# template.net
KiCad netlist of a schematic drawn in EAGLE
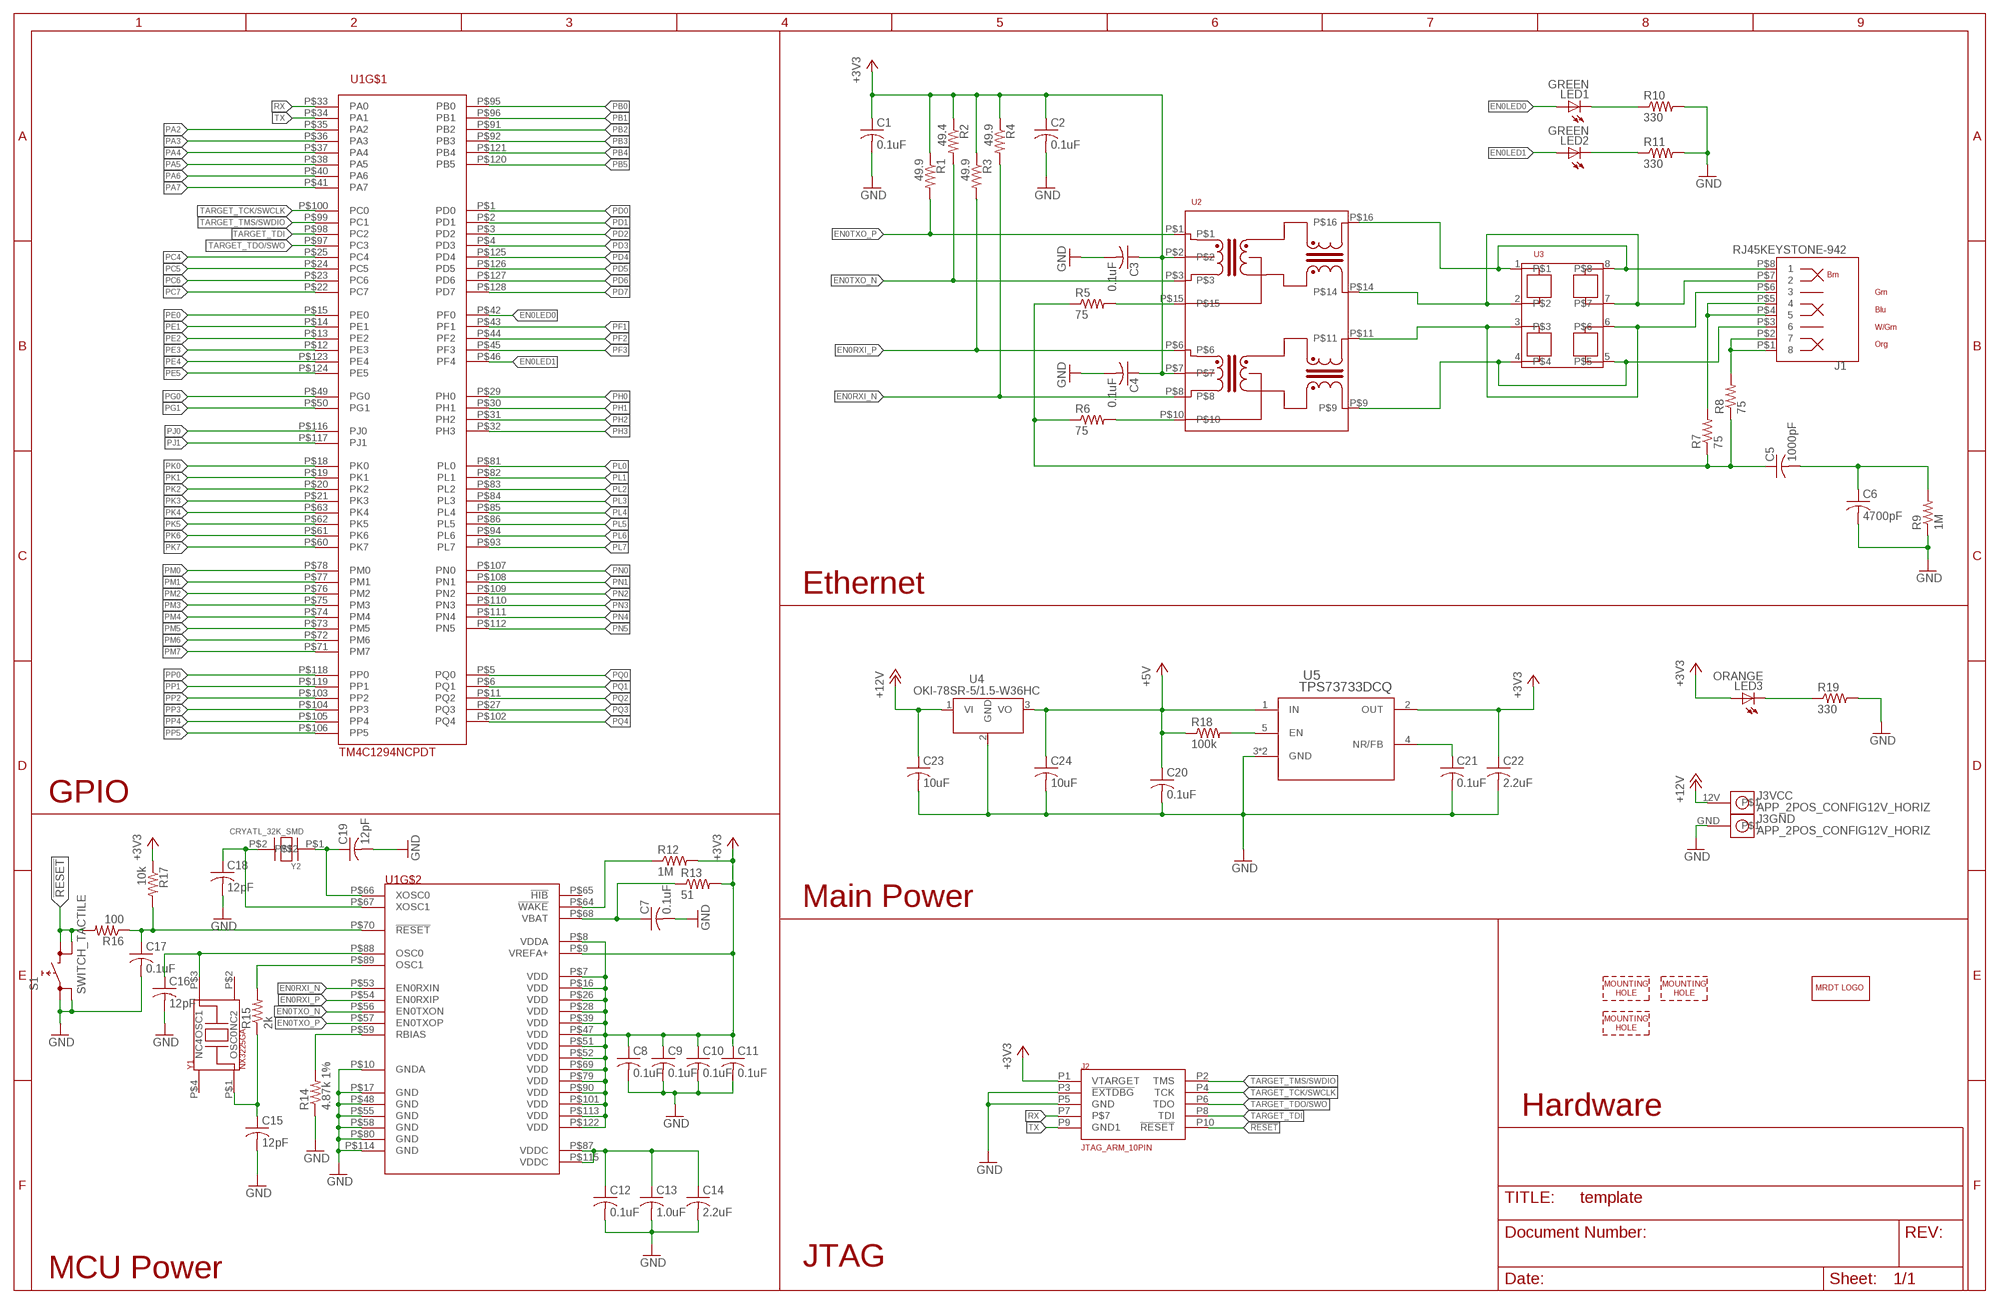
[diagram p0: schematic, sheet 1]

(export (version "E")
  (design (tool "Eeschema 10.0.6"))
  (components
    (comp (ref "C1")
      (value "0.1uF")
      (footprint "eagle-import:C0603")
      (libsource (lib "eagle-import") (part "C-USC0603"))
    )
    (comp (ref "C2")
      (value "0.1uF")
      (footprint "eagle-import:C0603")
      (libsource (lib "eagle-import") (part "C-USC0603"))
    )
    (comp (ref "C3")
      (value "0.1uF")
      (footprint "eagle-import:C0603")
      (libsource (lib "eagle-import") (part "C-USC0603"))
    )
    (comp (ref "C4")
      (value "0.1uF")
      (footprint "eagle-import:C0603")
      (libsource (lib "eagle-import") (part "C-USC0603"))
    )
    (comp (ref "C5")
      (value "1000pF")
      (footprint "eagle-import:C0603")
      (libsource (lib "eagle-import") (part "C-USC0603"))
    )
    (comp (ref "C6")
      (value "4700pF")
      (footprint "eagle-import:C1206")
      (libsource (lib "eagle-import") (part "C-USC1206"))
    )
    (comp (ref "C7")
      (value "0.1uF")
      (footprint "eagle-import:C0603")
      (libsource (lib "eagle-import") (part "C-USC0603"))
    )
    (comp (ref "C8")
      (value "0.1uF")
      (footprint "eagle-import:C0603")
      (libsource (lib "eagle-import") (part "C-USC0603"))
    )
    (comp (ref "C9")
      (value "0.1uF")
      (footprint "eagle-import:C0603")
      (libsource (lib "eagle-import") (part "C-USC0603"))
    )
    (comp (ref "C10")
      (value "0.1uF")
      (footprint "eagle-import:C0603")
      (libsource (lib "eagle-import") (part "C-USC0603"))
    )
    (comp (ref "C11")
      (value "0.1uF")
      (footprint "eagle-import:C0603")
      (libsource (lib "eagle-import") (part "C-USC0603"))
    )
    (comp (ref "C12")
      (value "0.1uF")
      (footprint "eagle-import:C0603")
      (libsource (lib "eagle-import") (part "C-USC0603"))
    )
    (comp (ref "C13")
      (value "1.0uF")
      (footprint "eagle-import:C0603")
      (libsource (lib "eagle-import") (part "C-USC0603"))
    )
    (comp (ref "C14")
      (value "2.2uF")
      (footprint "eagle-import:C0603")
      (libsource (lib "eagle-import") (part "C-USC0603"))
    )
    (comp (ref "C15")
      (value "12pF")
      (footprint "eagle-import:C0603")
      (libsource (lib "eagle-import") (part "C-USC0603"))
    )
    (comp (ref "C16")
      (value "12pF")
      (footprint "eagle-import:C0603")
      (libsource (lib "eagle-import") (part "C-USC0603"))
    )
    (comp (ref "C17")
      (value "0.1uF")
      (footprint "eagle-import:C0603")
      (libsource (lib "eagle-import") (part "C-USC0603"))
    )
    (comp (ref "C18")
      (value "12pF")
      (footprint "eagle-import:C0603")
      (libsource (lib "eagle-import") (part "C-USC0603"))
    )
    (comp (ref "C19")
      (value "12pF")
      (footprint "eagle-import:C0603")
      (libsource (lib "eagle-import") (part "C-USC0603"))
    )
    (comp (ref "C20")
      (value "0.1uF")
      (footprint "eagle-import:C0603")
      (libsource (lib "eagle-import") (part "C-USC0603"))
    )
    (comp (ref "C21")
      (value "0.1uF")
      (footprint "eagle-import:C0603")
      (libsource (lib "eagle-import") (part "C-USC0603"))
    )
    (comp (ref "C22")
      (value "2.2uF")
      (footprint "eagle-import:C0603")
      (libsource (lib "eagle-import") (part "C-USC0603"))
    )
    (comp (ref "C23")
      (value "10uF")
      (footprint "eagle-import:C0603")
      (libsource (lib "eagle-import") (part "C-USC0603"))
    )
    (comp (ref "C24")
      (value "10uF")
      (footprint "eagle-import:C0603")
      (libsource (lib "eagle-import") (part "C-USC0603"))
    )
    (comp (ref "J1")
      (value "RJ45KEYSTONE-942")
      (footprint "eagle-import:KEYSTONE-942")
      (libsource (lib "eagle-import") (part "RJ45KEYSTONE-942"))
    )
    (comp (ref "J2")
      (value "JTAG_ARM_10PIN")
      (footprint "eagle-import:CON_2X5_50MIL")
      (fields (field (name "PARTNO") "M50-3600542 "))
      (libsource (lib "eagle-import") (part "JTAG_ARM_10PIN"))
    )
    (comp (ref "J3")
      (value "APP_2POS_CONFIG12V_HORIZ")
      (footprint "eagle-import:APP45_12V_HORIZ_CONFIG")
      (libsource (lib "eagle-import") (part "APP_2POS_CONFIG12V_HORIZ"))
    )
    (comp (ref "LED1")
      (value "GREEN")
      (footprint "eagle-import:CHIP-LED0603")
      (libsource (lib "eagle-import") (part "LEDCHIP-LED0603"))
    )
    (comp (ref "LED2")
      (value "GREEN")
      (footprint "eagle-import:CHIP-LED0603")
      (libsource (lib "eagle-import") (part "LEDCHIP-LED0603"))
    )
    (comp (ref "LED3")
      (value "ORANGE")
      (footprint "eagle-import:CHIP-LED0603")
      (libsource (lib "eagle-import") (part "LEDCHIP-LED0603"))
    )
    (comp (ref "R1")
      (value "49.9")
      (footprint "eagle-import:R0603")
      (libsource (lib "eagle-import") (part "R-US_R0603"))
    )
    (comp (ref "R2")
      (value "49.4")
      (footprint "eagle-import:R0603")
      (libsource (lib "eagle-import") (part "resistor_R-US_R0603"))
    )
    (comp (ref "R3")
      (value "49.9")
      (footprint "eagle-import:R0603")
      (libsource (lib "eagle-import") (part "resistor_R-US_R0603"))
    )
    (comp (ref "R4")
      (value "49.9")
      (footprint "eagle-import:R0603")
      (libsource (lib "eagle-import") (part "resistor_R-US_R0603"))
    )
    (comp (ref "R5")
      (value "75")
      (footprint "eagle-import:R0603")
      (libsource (lib "eagle-import") (part "resistor_R-US_R0603"))
    )
    (comp (ref "R6")
      (value "75")
      (footprint "eagle-import:R0603")
      (libsource (lib "eagle-import") (part "resistor_R-US_R0603"))
    )
    (comp (ref "R7")
      (value "75")
      (footprint "eagle-import:R0603")
      (libsource (lib "eagle-import") (part "resistor_R-US_R0603"))
    )
    (comp (ref "R8")
      (value "75")
      (footprint "eagle-import:R0603")
      (libsource (lib "eagle-import") (part "resistor_R-US_R0603"))
    )
    (comp (ref "R9")
      (value "1M")
      (footprint "eagle-import:R1206")
      (libsource (lib "eagle-import") (part "resistor_R-US_R1206"))
    )
    (comp (ref "R10")
      (value "330")
      (footprint "eagle-import:R0603")
      (libsource (lib "eagle-import") (part "resistor_R-US_R0603"))
    )
    (comp (ref "R11")
      (value "330")
      (footprint "eagle-import:R0603")
      (libsource (lib "eagle-import") (part "resistor_R-US_R0603"))
    )
    (comp (ref "R12")
      (value "1M")
      (footprint "eagle-import:R0603")
      (libsource (lib "eagle-import") (part "resistor_R-US_R0603"))
    )
    (comp (ref "R13")
      (value "51")
      (footprint "eagle-import:R0603")
      (libsource (lib "eagle-import") (part "resistor_R-US_R0603"))
    )
    (comp (ref "R14")
      (value "4.87k 1%")
      (footprint "eagle-import:R0603")
      (libsource (lib "eagle-import") (part "resistor_R-US_R0603"))
    )
    (comp (ref "R15")
      (value "2k")
      (footprint "eagle-import:R0603")
      (libsource (lib "eagle-import") (part "resistor_R-US_R0603"))
    )
    (comp (ref "R16")
      (value "100")
      (footprint "eagle-import:R0603")
      (libsource (lib "eagle-import") (part "resistor_R-US_R0603"))
    )
    (comp (ref "R17")
      (value "10k")
      (footprint "eagle-import:R0603")
      (libsource (lib "eagle-import") (part "resistor_R-US_R0603"))
    )
    (comp (ref "R18")
      (value "100k")
      (footprint "eagle-import:R0603")
      (libsource (lib "eagle-import") (part "resistor_R-US_R0603"))
    )
    (comp (ref "R19")
      (value "330")
      (footprint "eagle-import:R0603")
      (libsource (lib "eagle-import") (part "resistor_R-US_R0603"))
    )
    (comp (ref "S1")
      (value "SWITCH_TACTILE")
      (footprint "eagle-import:SWITCH_6MM_6MM_TE_CON_SMD")
      (libsource (lib "eagle-import") (part "SWITCH_TACTILE"))
    )
    (comp (ref "U$1")
      (value "MRDT_LOGO")
      (footprint "eagle-import:MRDT_LOGO")
      (libsource (lib "eagle-import") (part "MRDT_LOGO"))
    )
    (comp (ref "U$2")
      (value "MOUNTING_HOLE#6")
      (footprint "eagle-import:#6_SCREW")
      (libsource (lib "eagle-import") (part "MOUNTING_HOLE#6"))
    )
    (comp (ref "U$3")
      (value "MOUNTING_HOLE#6")
      (footprint "eagle-import:#6_SCREW")
      (libsource (lib "eagle-import") (part "MOUNTING_HOLE#6"))
    )
    (comp (ref "U$4")
      (value "MOUNTING_HOLE#6")
      (footprint "eagle-import:#6_SCREW")
      (libsource (lib "eagle-import") (part "MOUNTING_HOLE#6"))
    )
    (comp (ref "U1")
      (value "TM4C1294NCPDT")
      (footprint "eagle-import:TQFP-128")
      (libsource (lib "eagle-import") (part "TM4C1294NCPDT"))
    )
    (comp (ref "U2")
      (value "HX1198FNL")
      (footprint "eagle-import:HX1198FNL")
      (libsource (lib "eagle-import") (part "HX1198FNL"))
    )
    (comp (ref "U3")
      (value "SLVU2.8-4")
      (footprint "eagle-import:SOIC8")
      (libsource (lib "eagle-import") (part "SLVU2.8-4"))
    )
    (comp (ref "U4")
      (value "OKI-78SR-5/1.5-W36HC")
      (footprint "eagle-import:OKI-78SR_HORIZ")
      (libsource (lib "eagle-import") (part "OKI-78SR-/1.5-W36?CH5"))
    )
    (comp (ref "U5")
      (value "TPS73733DCQ")
      (footprint "eagle-import:SOT-223-6")
      (libsource (lib "eagle-import") (part "TPS73733DCQ"))
    )
    (comp (ref "Y1")
      (value "NX3225GA")
      (footprint "eagle-import:NDK3.2X2.5")
      (libsource (lib "eagle-import") (part "NX3225GA"))
    )
    (comp (ref "Y2")
      (value "CRYATL_32K_SMD")
      (footprint "eagle-import:CRYSTAL_32K_SMD")
      (libsource (lib "eagle-import") (part "CRYATL_32K_SMD"))
    )
  )
  (nets
    (net (code "1") (name "+3V3") (class "Default")
      (node (ref "C1") (pin "1") (pinfunction "1_1") (pintype "passive"))
      (node (ref "C10") (pin "1") (pinfunction "1_1") (pintype "passive"))
      (node (ref "C11") (pin "1") (pinfunction "1_1") (pintype "passive"))
      (node (ref "C2") (pin "1") (pinfunction "1_1") (pintype "passive"))
      (node (ref "C22") (pin "1") (pinfunction "1_1") (pintype "passive"))
      (node (ref "C3") (pin "1") (pinfunction "1_1") (pintype "passive"))
      (node (ref "C4") (pin "1") (pinfunction "1_1") (pintype "passive"))
      (node (ref "C8") (pin "1") (pinfunction "1_1") (pintype "passive"))
      (node (ref "C9") (pin "1") (pinfunction "1_1") (pintype "passive"))
      (node (ref "J2") (pin "P1") (pinfunction "VTARGET_P1") (pintype "bidirectional"))
      (node (ref "LED3") (pin "A") (pinfunction "A_A") (pintype "passive"))
      (node (ref "R1") (pin "1") (pinfunction "1_1") (pintype "passive"))
      (node (ref "R12") (pin "2") (pinfunction "2_2") (pintype "passive"))
      (node (ref "R13") (pin "2") (pinfunction "2_2") (pintype "passive"))
      (node (ref "R17") (pin "1") (pinfunction "1_1") (pintype "passive"))
      (node (ref "R2") (pin "1") (pinfunction "1_1") (pintype "passive"))
      (node (ref "R3") (pin "1") (pinfunction "1_1") (pintype "passive"))
      (node (ref "R4") (pin "1") (pinfunction "1_1") (pintype "passive"))
      (node (ref "U1") (pin "P$101") (pinfunction "VDD_P$101") (pintype "bidirectional"))
      (node (ref "U1") (pin "P$113") (pinfunction "VDD_P$113") (pintype "bidirectional"))
      (node (ref "U1") (pin "P$122") (pinfunction "VDD_P$122") (pintype "bidirectional"))
      (node (ref "U1") (pin "P$16") (pinfunction "VDD_P$16") (pintype "bidirectional"))
      (node (ref "U1") (pin "P$26") (pinfunction "VDD_P$26") (pintype "bidirectional"))
      (node (ref "U1") (pin "P$28") (pinfunction "VDD_P$28") (pintype "bidirectional"))
      (node (ref "U1") (pin "P$39") (pinfunction "VDD_P$39") (pintype "bidirectional"))
      (node (ref "U1") (pin "P$47") (pinfunction "VDD_P$47") (pintype "bidirectional"))
      (node (ref "U1") (pin "P$51") (pinfunction "VDD_P$51") (pintype "bidirectional"))
      (node (ref "U1") (pin "P$52") (pinfunction "VDD_P$52") (pintype "bidirectional"))
      (node (ref "U1") (pin "P$69") (pinfunction "VDD_P$69") (pintype "bidirectional"))
      (node (ref "U1") (pin "P$7") (pinfunction "VDD_P$7") (pintype "bidirectional"))
      (node (ref "U1") (pin "P$79") (pinfunction "VDD_P$79") (pintype "bidirectional"))
      (node (ref "U1") (pin "P$8") (pinfunction "VDDA_P$8") (pintype "bidirectional"))
      (node (ref "U1") (pin "P$9") (pinfunction "VREFA+_P$9") (pintype "bidirectional"))
      (node (ref "U1") (pin "P$90") (pinfunction "VDD_P$90") (pintype "bidirectional"))
      (node (ref "U2") (pin "P$2") (pinfunction "P$2_P$2") (pintype "bidirectional"))
      (node (ref "U2") (pin "P$7") (pinfunction "P$7_P$7") (pintype "bidirectional"))
      (node (ref "U5") (pin "2") (pinfunction "OUT_2") (pintype "output"))
    )
    (net (code "2") (name "+5V") (class "Default")
      (node (ref "C20") (pin "1") (pinfunction "1_1") (pintype "passive"))
      (node (ref "C24") (pin "1") (pinfunction "1_1") (pintype "passive"))
      (node (ref "R18") (pin "1") (pinfunction "1_1") (pintype "passive"))
      (node (ref "U4") (pin "3") (pinfunction "VO_3") (pintype "bidirectional"))
      (node (ref "U5") (pin "1") (pinfunction "IN_1") (pintype "input"))
    )
    (net (code "3") (name "+12V") (class "Default")
      (node (ref "C23") (pin "1") (pinfunction "1_1") (pintype "passive"))
      (node (ref "J3") (pin "12V") (pinfunction "P$1_12V") (pintype "bidirectional"))
      (node (ref "U4") (pin "1") (pinfunction "VI_1") (pintype "bidirectional"))
    )
    (net (code "4") (name "/~{RESET}") (class "Default")
      (node (ref "J2") (pin "P10") (pinfunction "~{RESET}_P10") (pintype "bidirectional"))
      (node (ref "R16") (pin "2") (pinfunction "2_2") (pintype "passive"))
      (node (ref "S1") (pin "P$3") (pinfunction "1_P$3") (pintype "passive"))
      (node (ref "S1") (pin "P$4") (pinfunction "1_P$4") (pintype "passive"))
    )
    (net (code "5") (name "EN0LED0") (class "Default")
      (node (ref "LED1") (pin "A") (pinfunction "A_A") (pintype "passive"))
      (node (ref "U1") (pin "P$42") (pinfunction "PF0_P$42") (pintype "bidirectional"))
    )
    (net (code "6") (name "EN0LED1") (class "Default")
      (node (ref "LED2") (pin "A") (pinfunction "A_A") (pintype "passive"))
      (node (ref "U1") (pin "P$46") (pinfunction "PF4_P$46") (pintype "bidirectional"))
    )
    (net (code "7") (name "EN0RXI_N") (class "Default")
      (node (ref "R4") (pin "2") (pinfunction "2_2") (pintype "passive"))
      (node (ref "U1") (pin "P$53") (pinfunction "EN0RXIN_P$53") (pintype "bidirectional"))
      (node (ref "U2") (pin "P$8") (pinfunction "P$8_P$8") (pintype "bidirectional"))
    )
    (net (code "8") (name "EN0RXI_P") (class "Default")
      (node (ref "R3") (pin "2") (pinfunction "2_2") (pintype "passive"))
      (node (ref "U1") (pin "P$54") (pinfunction "EN0RXIP_P$54") (pintype "bidirectional"))
      (node (ref "U2") (pin "P$6") (pinfunction "P$6_P$6") (pintype "bidirectional"))
    )
    (net (code "9") (name "EN0TXO_N") (class "Default")
      (node (ref "R2") (pin "2") (pinfunction "2_2") (pintype "passive"))
      (node (ref "U1") (pin "P$56") (pinfunction "EN0TXON_P$56") (pintype "bidirectional"))
      (node (ref "U2") (pin "P$3") (pinfunction "P$3_P$3") (pintype "bidirectional"))
    )
    (net (code "10") (name "EN0TXO_P") (class "Default")
      (node (ref "R1") (pin "2") (pinfunction "2_2") (pintype "passive"))
      (node (ref "U1") (pin "P$57") (pinfunction "EN0TXOP_P$57") (pintype "bidirectional"))
      (node (ref "U2") (pin "P$1") (pinfunction "P$1_P$1") (pintype "bidirectional"))
    )
    (net (code "11") (name "GND") (class "Default")
      (node (ref "C1") (pin "2") (pinfunction "2_2") (pintype "passive"))
      (node (ref "C10") (pin "2") (pinfunction "2_2") (pintype "passive"))
      (node (ref "C11") (pin "2") (pinfunction "2_2") (pintype "passive"))
      (node (ref "C12") (pin "2") (pinfunction "2_2") (pintype "passive"))
      (node (ref "C13") (pin "2") (pinfunction "2_2") (pintype "passive"))
      (node (ref "C14") (pin "2") (pinfunction "2_2") (pintype "passive"))
      (node (ref "C15") (pin "2") (pinfunction "2_2") (pintype "passive"))
      (node (ref "C16") (pin "2") (pinfunction "2_2") (pintype "passive"))
      (node (ref "C17") (pin "2") (pinfunction "2_2") (pintype "passive"))
      (node (ref "C18") (pin "2") (pinfunction "2_2") (pintype "passive"))
      (node (ref "C19") (pin "2") (pinfunction "2_2") (pintype "passive"))
      (node (ref "C2") (pin "2") (pinfunction "2_2") (pintype "passive"))
      (node (ref "C20") (pin "2") (pinfunction "2_2") (pintype "passive"))
      (node (ref "C21") (pin "2") (pinfunction "2_2") (pintype "passive"))
      (node (ref "C22") (pin "2") (pinfunction "2_2") (pintype "passive"))
      (node (ref "C23") (pin "2") (pinfunction "2_2") (pintype "passive"))
      (node (ref "C24") (pin "2") (pinfunction "2_2") (pintype "passive"))
      (node (ref "C3") (pin "2") (pinfunction "2_2") (pintype "passive"))
      (node (ref "C4") (pin "2") (pinfunction "2_2") (pintype "passive"))
      (node (ref "C6") (pin "2") (pinfunction "2_2") (pintype "passive"))
      (node (ref "C7") (pin "2") (pinfunction "2_2") (pintype "passive"))
      (node (ref "C8") (pin "2") (pinfunction "2_2") (pintype "passive"))
      (node (ref "C9") (pin "2") (pinfunction "2_2") (pintype "passive"))
      (node (ref "J2") (pin "P3") (pinfunction "~{EXTDBG}_P3") (pintype "bidirectional"))
      (node (ref "J2") (pin "P5") (pinfunction "GND_P5") (pintype "bidirectional"))
      (node (ref "J3") (pin "GND") (pinfunction "P$1_GND") (pintype "bidirectional"))
      (node (ref "R10") (pin "2") (pinfunction "2_2") (pintype "passive"))
      (node (ref "R11") (pin "2") (pinfunction "2_2") (pintype "passive"))
      (node (ref "R14") (pin "1") (pinfunction "1_1") (pintype "passive"))
      (node (ref "R19") (pin "2") (pinfunction "2_2") (pintype "passive"))
      (node (ref "R9") (pin "1") (pinfunction "1_1") (pintype "passive"))
      (node (ref "S1") (pin "P$1") (pinfunction "0_P$1") (pintype "passive"))
      (node (ref "S1") (pin "P$2") (pinfunction "0_P$2") (pintype "passive"))
      (node (ref "U1") (pin "P$10") (pinfunction "GNDA_P$10") (pintype "bidirectional"))
      (node (ref "U1") (pin "P$114") (pinfunction "GND_P$114") (pintype "bidirectional"))
      (node (ref "U1") (pin "P$17") (pinfunction "GND_P$17") (pintype "bidirectional"))
      (node (ref "U1") (pin "P$48") (pinfunction "GND_P$48") (pintype "bidirectional"))
      (node (ref "U1") (pin "P$55") (pinfunction "GND_P$55") (pintype "bidirectional"))
      (node (ref "U1") (pin "P$58") (pinfunction "GND_P$58") (pintype "bidirectional"))
      (node (ref "U1") (pin "P$80") (pinfunction "GND_P$80") (pintype "bidirectional"))
      (node (ref "U4") (pin "2") (pinfunction "GND_2") (pintype "bidirectional"))
      (node (ref "U5") (pin "3") (pinfunction "GND_3") (pintype "power_in"))
      (node (ref "U5") (pin "6") (pinfunction "GND_6") (pintype "power_in"))
    )
    (net (code "12") (name "Net-(C5-Pad1)") (class "Default")
      (node (ref "C5") (pin "1") (pinfunction "1_1") (pintype "passive"))
      (node (ref "R5") (pin "1") (pinfunction "1_1") (pintype "passive"))
      (node (ref "R6") (pin "1") (pinfunction "1_1") (pintype "passive"))
      (node (ref "R7") (pin "1") (pinfunction "1_1") (pintype "passive"))
      (node (ref "R8") (pin "1") (pinfunction "1_1") (pintype "passive"))
    )
    (net (code "13") (name "Net-(C5-Pad2)") (class "Default")
      (node (ref "C5") (pin "2") (pinfunction "2_2") (pintype "passive"))
      (node (ref "C6") (pin "1") (pinfunction "1_1") (pintype "passive"))
      (node (ref "R9") (pin "2") (pinfunction "2_2") (pintype "passive"))
    )
    (net (code "14") (name "Net-(C12-Pad1)") (class "Default")
      (node (ref "C12") (pin "1") (pinfunction "1_1") (pintype "passive"))
      (node (ref "C13") (pin "1") (pinfunction "1_1") (pintype "passive"))
      (node (ref "C14") (pin "1") (pinfunction "1_1") (pintype "passive"))
      (node (ref "U1") (pin "P$115") (pinfunction "VDDC_P$115") (pintype "bidirectional"))
      (node (ref "U1") (pin "P$87") (pinfunction "VDDC_P$87") (pintype "bidirectional"))
    )
    (net (code "15") (name "Net-(J1-1)") (class "Default")
      (node (ref "J1") (pin "P$8") (pinfunction "1_P$8") (pintype "bidirectional"))
      (node (ref "U2") (pin "P$16") (pinfunction "P$16_P$16") (pintype "bidirectional"))
      (node (ref "U3") (pin "1") (pinfunction "P$1_1") (pintype "bidirectional"))
      (node (ref "U3") (pin "8") (pinfunction "P$8_8") (pintype "bidirectional"))
    )
    (net (code "16") (name "Net-(J1-2)") (class "Default")
      (node (ref "J1") (pin "P$7") (pinfunction "2_P$7") (pintype "bidirectional"))
      (node (ref "U2") (pin "P$14") (pinfunction "P$14_P$14") (pintype "bidirectional"))
      (node (ref "U3") (pin "2") (pinfunction "P$2_2") (pintype "bidirectional"))
      (node (ref "U3") (pin "7") (pinfunction "P$7_7") (pintype "bidirectional"))
    )
    (net (code "17") (name "Net-(J1-3)") (class "Default")
      (node (ref "J1") (pin "P$6") (pinfunction "3_P$6") (pintype "bidirectional"))
      (node (ref "U2") (pin "P$11") (pinfunction "P$11_P$11") (pintype "bidirectional"))
      (node (ref "U3") (pin "3") (pinfunction "P$3_3") (pintype "bidirectional"))
      (node (ref "U3") (pin "6") (pinfunction "P$6_6") (pintype "bidirectional"))
    )
    (net (code "18") (name "Net-(J1-4)") (class "Default")
      (node (ref "J1") (pin "P$4") (pinfunction "5_P$4") (pintype "bidirectional"))
      (node (ref "J1") (pin "P$5") (pinfunction "4_P$5") (pintype "bidirectional"))
      (node (ref "R7") (pin "2") (pinfunction "2_2") (pintype "passive"))
    )
    (net (code "19") (name "Net-(J1-6)") (class "Default")
      (node (ref "J1") (pin "P$3") (pinfunction "6_P$3") (pintype "bidirectional"))
      (node (ref "U2") (pin "P$9") (pinfunction "P$9_P$9") (pintype "bidirectional"))
      (node (ref "U3") (pin "4") (pinfunction "P$4_4") (pintype "bidirectional"))
      (node (ref "U3") (pin "5") (pinfunction "P$5_5") (pintype "bidirectional"))
    )
    (net (code "20") (name "Net-(J1-7)") (class "Default")
      (node (ref "J1") (pin "P$1") (pinfunction "8_P$1") (pintype "bidirectional"))
      (node (ref "J1") (pin "P$2") (pinfunction "7_P$2") (pintype "bidirectional"))
      (node (ref "R8") (pin "2") (pinfunction "2_2") (pintype "passive"))
    )
    (net (code "21") (name "Net-(LED1-PadC)") (class "Default")
      (node (ref "LED1") (pin "C") (pinfunction "C_C") (pintype "passive"))
      (node (ref "R10") (pin "1") (pinfunction "1_1") (pintype "passive"))
    )
    (net (code "22") (name "Net-(LED2-PadC)") (class "Default")
      (node (ref "LED2") (pin "C") (pinfunction "C_C") (pintype "passive"))
      (node (ref "R11") (pin "1") (pinfunction "1_1") (pintype "passive"))
    )
    (net (code "23") (name "Net-(LED3-PadC)") (class "Default")
      (node (ref "LED3") (pin "C") (pinfunction "C_C") (pintype "passive"))
      (node (ref "R19") (pin "1") (pinfunction "1_1") (pintype "passive"))
    )
    (net (code "24") (name "Net-(R5-Pad2)") (class "Default")
      (node (ref "R5") (pin "2") (pinfunction "2_2") (pintype "passive"))
      (node (ref "U2") (pin "P$15") (pinfunction "P$15_P$15") (pintype "bidirectional"))
    )
    (net (code "25") (name "Net-(R6-Pad2)") (class "Default")
      (node (ref "R6") (pin "2") (pinfunction "2_2") (pintype "passive"))
      (node (ref "U2") (pin "P$10") (pinfunction "P$10_P$10") (pintype "bidirectional"))
    )
    (net (code "26") (name "Net-(U1B-OSC0)") (class "Default")
      (node (ref "C16") (pin "1") (pinfunction "1_1") (pintype "passive"))
      (node (ref "U1") (pin "P$88") (pinfunction "OSC0_P$88") (pintype "bidirectional"))
      (node (ref "Y1") (pin "P$3") (pinfunction "OSC1_P$3") (pintype "bidirectional"))
    )
    (net (code "27") (name "Net-(U1B-OSC1)") (class "Default")
      (node (ref "R15") (pin "2") (pinfunction "2_2") (pintype "passive"))
      (node (ref "U1") (pin "P$89") (pinfunction "OSC1_P$89") (pintype "bidirectional"))
    )
    (net (code "28") (name "Net-(U1B-RBIAS)") (class "Default")
      (node (ref "R14") (pin "2") (pinfunction "2_2") (pintype "passive"))
      (node (ref "U1") (pin "P$59") (pinfunction "RBIAS_P$59") (pintype "bidirectional"))
    )
    (net (code "29") (name "Net-(U1B-VBAT)") (class "Default")
      (node (ref "C7") (pin "1") (pinfunction "1_1") (pintype "passive"))
      (node (ref "R13") (pin "1") (pinfunction "1_1") (pintype "passive"))
      (node (ref "U1") (pin "P$68") (pinfunction "VBAT_P$68") (pintype "bidirectional"))
    )
    (net (code "30") (name "Net-(U1B-XOSC0)") (class "Default")
      (node (ref "C19") (pin "1") (pinfunction "1_1") (pintype "passive"))
      (node (ref "U1") (pin "P$66") (pinfunction "XOSC0_P$66") (pintype "bidirectional"))
      (node (ref "Y2") (pin "P$1") (pinfunction "P$1_P$1") (pintype "bidirectional"))
    )
    (net (code "31") (name "Net-(U1B-XOSC1)") (class "Default")
      (node (ref "C18") (pin "1") (pinfunction "1_1") (pintype "passive"))
      (node (ref "U1") (pin "P$67") (pinfunction "XOSC1_P$67") (pintype "bidirectional"))
      (node (ref "Y2") (pin "P$2") (pinfunction "P$2_P$2") (pintype "bidirectional"))
    )
    (net (code "32") (name "Net-(U1B-~{RESET})") (class "Default")
      (node (ref "C17") (pin "1") (pinfunction "1_1") (pintype "passive"))
      (node (ref "R16") (pin "1") (pinfunction "1_1") (pintype "passive"))
      (node (ref "R17") (pin "2") (pinfunction "2_2") (pintype "passive"))
      (node (ref "U1") (pin "P$70") (pinfunction "~{RESET}_P$70") (pintype "bidirectional"))
    )
    (net (code "33") (name "Net-(U1B-~{WAKE})") (class "Default")
      (node (ref "R12") (pin "1") (pinfunction "1_1") (pintype "passive"))
      (node (ref "U1") (pin "P$64") (pinfunction "~{WAKE}_P$64") (pintype "bidirectional"))
    )
    (net (code "34") (name "Net-(U5-EN)") (class "Default")
      (node (ref "R18") (pin "2") (pinfunction "2_2") (pintype "passive"))
      (node (ref "U5") (pin "5") (pinfunction "EN_5") (pintype "passive"))
    )
    (net (code "35") (name "Net-(U5-NR{slash}FB)") (class "Default")
      (node (ref "C21") (pin "1") (pinfunction "1_1") (pintype "passive"))
      (node (ref "U5") (pin "4") (pinfunction "NR/FB_4") (pintype "bidirectional"))
    )
    (net (code "36") (name "Net-(Y1-OSC0)") (class "Default")
      (node (ref "C15") (pin "1") (pinfunction "1_1") (pintype "passive"))
      (node (ref "R15") (pin "1") (pinfunction "1_1") (pintype "passive"))
      (node (ref "Y1") (pin "P$1") (pinfunction "OSC0_P$1") (pintype "bidirectional"))
    )
    (net (code "37") (name "PA2") (class "Default")
      (node (ref "U1") (pin "P$35") (pinfunction "PA2_P$35") (pintype "bidirectional"))
    )
    (net (code "38") (name "PA3") (class "Default")
      (node (ref "U1") (pin "P$36") (pinfunction "PA3_P$36") (pintype "bidirectional"))
    )
    (net (code "39") (name "PA4") (class "Default")
      (node (ref "U1") (pin "P$37") (pinfunction "PA4_P$37") (pintype "bidirectional"))
    )
    (net (code "40") (name "PA5") (class "Default")
      (node (ref "U1") (pin "P$38") (pinfunction "PA5_P$38") (pintype "bidirectional"))
    )
    (net (code "41") (name "PA6") (class "Default")
      (node (ref "U1") (pin "P$40") (pinfunction "PA6_P$40") (pintype "bidirectional"))
    )
    (net (code "42") (name "PA7") (class "Default")
      (node (ref "U1") (pin "P$41") (pinfunction "PA7_P$41") (pintype "bidirectional"))
    )
    (net (code "43") (name "PB0") (class "Default")
      (node (ref "U1") (pin "P$95") (pinfunction "PB0_P$95") (pintype "bidirectional"))
    )
    (net (code "44") (name "PB1") (class "Default")
      (node (ref "U1") (pin "P$96") (pinfunction "PB1_P$96") (pintype "bidirectional"))
    )
    (net (code "45") (name "PB2") (class "Default")
      (node (ref "U1") (pin "P$91") (pinfunction "PB2_P$91") (pintype "bidirectional"))
    )
    (net (code "46") (name "PB3") (class "Default")
      (node (ref "U1") (pin "P$92") (pinfunction "PB3_P$92") (pintype "bidirectional"))
    )
    (net (code "47") (name "PB4") (class "Default")
      (node (ref "U1") (pin "P$121") (pinfunction "PB4_P$121") (pintype "bidirectional"))
    )
    (net (code "48") (name "PB5") (class "Default")
      (node (ref "U1") (pin "P$120") (pinfunction "PB5_P$120") (pintype "bidirectional"))
    )
    (net (code "49") (name "PC4") (class "Default")
      (node (ref "U1") (pin "P$25") (pinfunction "PC4_P$25") (pintype "bidirectional"))
    )
    (net (code "50") (name "PC5") (class "Default")
      (node (ref "U1") (pin "P$24") (pinfunction "PC5_P$24") (pintype "bidirectional"))
    )
    (net (code "51") (name "PC6") (class "Default")
      (node (ref "U1") (pin "P$23") (pinfunction "PC6_P$23") (pintype "bidirectional"))
    )
    (net (code "52") (name "PC7") (class "Default")
      (node (ref "U1") (pin "P$22") (pinfunction "PC7_P$22") (pintype "bidirectional"))
    )
    (net (code "53") (name "PD0") (class "Default")
      (node (ref "U1") (pin "P$1") (pinfunction "PD0_P$1") (pintype "bidirectional"))
    )
    (net (code "54") (name "PD1") (class "Default")
      (node (ref "U1") (pin "P$2") (pinfunction "PD1_P$2") (pintype "bidirectional"))
    )
    (net (code "55") (name "PD2") (class "Default")
      (node (ref "U1") (pin "P$3") (pinfunction "PD2_P$3") (pintype "bidirectional"))
    )
    (net (code "56") (name "PD3") (class "Default")
      (node (ref "U1") (pin "P$4") (pinfunction "PD3_P$4") (pintype "bidirectional"))
    )
    (net (code "57") (name "PD4") (class "Default")
      (node (ref "U1") (pin "P$125") (pinfunction "PD4_P$125") (pintype "bidirectional"))
    )
    (net (code "58") (name "PD5") (class "Default")
      (node (ref "U1") (pin "P$126") (pinfunction "PD5_P$126") (pintype "bidirectional"))
    )
    (net (code "59") (name "PD6") (class "Default")
      (node (ref "U1") (pin "P$127") (pinfunction "PD6_P$127") (pintype "bidirectional"))
    )
    (net (code "60") (name "PD7") (class "Default")
      (node (ref "U1") (pin "P$128") (pinfunction "PD7_P$128") (pintype "bidirectional"))
    )
    (net (code "61") (name "PE0") (class "Default")
      (node (ref "U1") (pin "P$15") (pinfunction "PE0_P$15") (pintype "bidirectional"))
    )
    (net (code "62") (name "PE1") (class "Default")
      (node (ref "U1") (pin "P$14") (pinfunction "PE1_P$14") (pintype "bidirectional"))
    )
    (net (code "63") (name "PE2") (class "Default")
      (node (ref "U1") (pin "P$13") (pinfunction "PE2_P$13") (pintype "bidirectional"))
    )
    (net (code "64") (name "PE3") (class "Default")
      (node (ref "U1") (pin "P$12") (pinfunction "PE3_P$12") (pintype "bidirectional"))
    )
    (net (code "65") (name "PE4") (class "Default")
      (node (ref "U1") (pin "P$123") (pinfunction "PE4_P$123") (pintype "bidirectional"))
    )
    (net (code "66") (name "PE5") (class "Default")
      (node (ref "U1") (pin "P$124") (pinfunction "PE5_P$124") (pintype "bidirectional"))
    )
    (net (code "67") (name "PF1") (class "Default")
      (node (ref "U1") (pin "P$43") (pinfunction "PF1_P$43") (pintype "bidirectional"))
    )
    (net (code "68") (name "PF2") (class "Default")
      (node (ref "U1") (pin "P$44") (pinfunction "PF2_P$44") (pintype "bidirectional"))
    )
    (net (code "69") (name "PF3") (class "Default")
      (node (ref "U1") (pin "P$45") (pinfunction "PF3_P$45") (pintype "bidirectional"))
    )
    (net (code "70") (name "PG0") (class "Default")
      (node (ref "U1") (pin "P$49") (pinfunction "PG0_P$49") (pintype "bidirectional"))
    )
    (net (code "71") (name "PG1") (class "Default")
      (node (ref "U1") (pin "P$50") (pinfunction "PG1_P$50") (pintype "bidirectional"))
    )
    (net (code "72") (name "PH0") (class "Default")
      (node (ref "U1") (pin "P$29") (pinfunction "PH0_P$29") (pintype "bidirectional"))
    )
    (net (code "73") (name "PH1") (class "Default")
      (node (ref "U1") (pin "P$30") (pinfunction "PH1_P$30") (pintype "bidirectional"))
    )
    (net (code "74") (name "PH2") (class "Default")
      (node (ref "U1") (pin "P$31") (pinfunction "PH2_P$31") (pintype "bidirectional"))
    )
    (net (code "75") (name "PH3") (class "Default")
      (node (ref "U1") (pin "P$32") (pinfunction "PH3_P$32") (pintype "bidirectional"))
    )
    (net (code "76") (name "PJ0") (class "Default")
      (node (ref "U1") (pin "P$116") (pinfunction "PJ0_P$116") (pintype "bidirectional"))
    )
    (net (code "77") (name "PJ1") (class "Default")
      (node (ref "U1") (pin "P$117") (pinfunction "PJ1_P$117") (pintype "bidirectional"))
    )
    (net (code "78") (name "PK0") (class "Default")
      (node (ref "U1") (pin "P$18") (pinfunction "PK0_P$18") (pintype "bidirectional"))
    )
    (net (code "79") (name "PK1") (class "Default")
      (node (ref "U1") (pin "P$19") (pinfunction "PK1_P$19") (pintype "bidirectional"))
    )
    (net (code "80") (name "PK2") (class "Default")
      (node (ref "U1") (pin "P$20") (pinfunction "PK2_P$20") (pintype "bidirectional"))
    )
    (net (code "81") (name "PK3") (class "Default")
      (node (ref "U1") (pin "P$21") (pinfunction "PK3_P$21") (pintype "bidirectional"))
    )
    (net (code "82") (name "PK4") (class "Default")
      (node (ref "U1") (pin "P$63") (pinfunction "PK4_P$63") (pintype "bidirectional"))
    )
    (net (code "83") (name "PK5") (class "Default")
      (node (ref "U1") (pin "P$62") (pinfunction "PK5_P$62") (pintype "bidirectional"))
    )
    (net (code "84") (name "PK6") (class "Default")
      (node (ref "U1") (pin "P$61") (pinfunction "PK6_P$61") (pintype "bidirectional"))
    )
    (net (code "85") (name "PK7") (class "Default")
      (node (ref "U1") (pin "P$60") (pinfunction "PK7_P$60") (pintype "bidirectional"))
    )
    (net (code "86") (name "PL0") (class "Default")
      (node (ref "U1") (pin "P$81") (pinfunction "PL0_P$81") (pintype "bidirectional"))
    )
    (net (code "87") (name "PL1") (class "Default")
      (node (ref "U1") (pin "P$82") (pinfunction "PL1_P$82") (pintype "bidirectional"))
    )
    (net (code "88") (name "PL2") (class "Default")
      (node (ref "U1") (pin "P$83") (pinfunction "PL2_P$83") (pintype "bidirectional"))
    )
    (net (code "89") (name "PL3") (class "Default")
      (node (ref "U1") (pin "P$84") (pinfunction "PL3_P$84") (pintype "bidirectional"))
    )
    (net (code "90") (name "PL4") (class "Default")
      (node (ref "U1") (pin "P$85") (pinfunction "PL4_P$85") (pintype "bidirectional"))
    )
    (net (code "91") (name "PL5") (class "Default")
      (node (ref "U1") (pin "P$86") (pinfunction "PL5_P$86") (pintype "bidirectional"))
    )
    (net (code "92") (name "PL6") (class "Default")
      (node (ref "U1") (pin "P$94") (pinfunction "PL6_P$94") (pintype "bidirectional"))
    )
    (net (code "93") (name "PL7") (class "Default")
      (node (ref "U1") (pin "P$93") (pinfunction "PL7_P$93") (pintype "bidirectional"))
    )
    (net (code "94") (name "PM0") (class "Default")
      (node (ref "U1") (pin "P$78") (pinfunction "PM0_P$78") (pintype "bidirectional"))
    )
    (net (code "95") (name "PM1") (class "Default")
      (node (ref "U1") (pin "P$77") (pinfunction "PM1_P$77") (pintype "bidirectional"))
    )
    (net (code "96") (name "PM2") (class "Default")
      (node (ref "U1") (pin "P$76") (pinfunction "PM2_P$76") (pintype "bidirectional"))
    )
    (net (code "97") (name "PM3") (class "Default")
      (node (ref "U1") (pin "P$75") (pinfunction "PM3_P$75") (pintype "bidirectional"))
    )
    (net (code "98") (name "PM4") (class "Default")
      (node (ref "U1") (pin "P$74") (pinfunction "PM4_P$74") (pintype "bidirectional"))
    )
    (net (code "99") (name "PM5") (class "Default")
      (node (ref "U1") (pin "P$73") (pinfunction "PM5_P$73") (pintype "bidirectional"))
    )
    (net (code "100") (name "PM6") (class "Default")
      (node (ref "U1") (pin "P$72") (pinfunction "PM6_P$72") (pintype "bidirectional"))
    )
    (net (code "101") (name "PM7") (class "Default")
      (node (ref "U1") (pin "P$71") (pinfunction "PM7_P$71") (pintype "bidirectional"))
    )
    (net (code "102") (name "PN0") (class "Default")
      (node (ref "U1") (pin "P$107") (pinfunction "PN0_P$107") (pintype "bidirectional"))
    )
    (net (code "103") (name "PN1") (class "Default")
      (node (ref "U1") (pin "P$108") (pinfunction "PN1_P$108") (pintype "bidirectional"))
    )
    (net (code "104") (name "PN2") (class "Default")
      (node (ref "U1") (pin "P$109") (pinfunction "PN2_P$109") (pintype "bidirectional"))
    )
    (net (code "105") (name "PN3") (class "Default")
      (node (ref "U1") (pin "P$110") (pinfunction "PN3_P$110") (pintype "bidirectional"))
    )
    (net (code "106") (name "PN4") (class "Default")
      (node (ref "U1") (pin "P$111") (pinfunction "PN4_P$111") (pintype "bidirectional"))
    )
    (net (code "107") (name "PN5") (class "Default")
      (node (ref "U1") (pin "P$112") (pinfunction "PN5_P$112") (pintype "bidirectional"))
    )
    (net (code "108") (name "PP0") (class "Default")
      (node (ref "U1") (pin "P$118") (pinfunction "PP0_P$118") (pintype "bidirectional"))
    )
    (net (code "109") (name "PP1") (class "Default")
      (node (ref "U1") (pin "P$119") (pinfunction "PP1_P$119") (pintype "bidirectional"))
    )
    (net (code "110") (name "PP2") (class "Default")
      (node (ref "U1") (pin "P$103") (pinfunction "PP2_P$103") (pintype "bidirectional"))
    )
    (net (code "111") (name "PP3") (class "Default")
      (node (ref "U1") (pin "P$104") (pinfunction "PP3_P$104") (pintype "bidirectional"))
    )
    (net (code "112") (name "PP4") (class "Default")
      (node (ref "U1") (pin "P$105") (pinfunction "PP4_P$105") (pintype "bidirectional"))
    )
    (net (code "113") (name "PP5") (class "Default")
      (node (ref "U1") (pin "P$106") (pinfunction "PP5_P$106") (pintype "bidirectional"))
    )
    (net (code "114") (name "PQ0") (class "Default")
      (node (ref "U1") (pin "P$5") (pinfunction "PQ0_P$5") (pintype "bidirectional"))
    )
    (net (code "115") (name "PQ1") (class "Default")
      (node (ref "U1") (pin "P$6") (pinfunction "PQ1_P$6") (pintype "bidirectional"))
    )
    (net (code "116") (name "PQ2") (class "Default")
      (node (ref "U1") (pin "P$11") (pinfunction "PQ2_P$11") (pintype "bidirectional"))
    )
    (net (code "117") (name "PQ3") (class "Default")
      (node (ref "U1") (pin "P$27") (pinfunction "PQ3_P$27") (pintype "bidirectional"))
    )
    (net (code "118") (name "PQ4") (class "Default")
      (node (ref "U1") (pin "P$102") (pinfunction "PQ4_P$102") (pintype "bidirectional"))
    )
    (net (code "119") (name "RX") (class "Default")
      (node (ref "J2") (pin "P7") (pinfunction "P$7_P7") (pintype "bidirectional"))
      (node (ref "U1") (pin "P$33") (pinfunction "PA0_P$33") (pintype "bidirectional"))
    )
    (net (code "120") (name "TARGET_TCK{slash}SWCLK") (class "Default")
      (node (ref "J2") (pin "P4") (pinfunction "TCK_P4") (pintype "bidirectional"))
      (node (ref "U1") (pin "P$100") (pinfunction "PC0_P$100") (pintype "bidirectional"))
    )
    (net (code "121") (name "TARGET_TDI") (class "Default")
      (node (ref "J2") (pin "P8") (pinfunction "TDI_P8") (pintype "bidirectional"))
      (node (ref "U1") (pin "P$98") (pinfunction "PC2_P$98") (pintype "bidirectional"))
    )
    (net (code "122") (name "TARGET_TDO{slash}SWO") (class "Default")
      (node (ref "J2") (pin "P6") (pinfunction "TDO_P6") (pintype "bidirectional"))
      (node (ref "U1") (pin "P$97") (pinfunction "PC3_P$97") (pintype "bidirectional"))
    )
    (net (code "123") (name "TARGET_TMS{slash}SWDIO") (class "Default")
      (node (ref "J2") (pin "P2") (pinfunction "TMS_P2") (pintype "bidirectional"))
      (node (ref "U1") (pin "P$99") (pinfunction "PC1_P$99") (pintype "bidirectional"))
    )
    (net (code "124") (name "TX") (class "Default")
      (node (ref "J2") (pin "P9") (pinfunction "GND1_P9") (pintype "bidirectional"))
      (node (ref "U1") (pin "P$34") (pinfunction "PA1_P$34") (pintype "bidirectional"))
    )
    (net (code "125") (name "unconnected-(U1B-~{HIB}-PadP$65)") (class "Default")
      (node (ref "U1") (pin "P$65") (pinfunction "~{HIB}_P$65") (pintype "bidirectional"))
    )
    (net (code "126") (name "unconnected-(Y1-NC2-PadP$2)") (class "Default")
      (node (ref "Y1") (pin "P$2") (pinfunction "NC2_P$2") (pintype "bidirectional"))
    )
    (net (code "127") (name "unconnected-(Y1-NC4-PadP$4)") (class "Default")
      (node (ref "Y1") (pin "P$4") (pinfunction "NC4_P$4") (pintype "bidirectional"))
    )
  )
)
